# multiOsh2.net
KiCad netlist of a schematic drawn in EAGLE
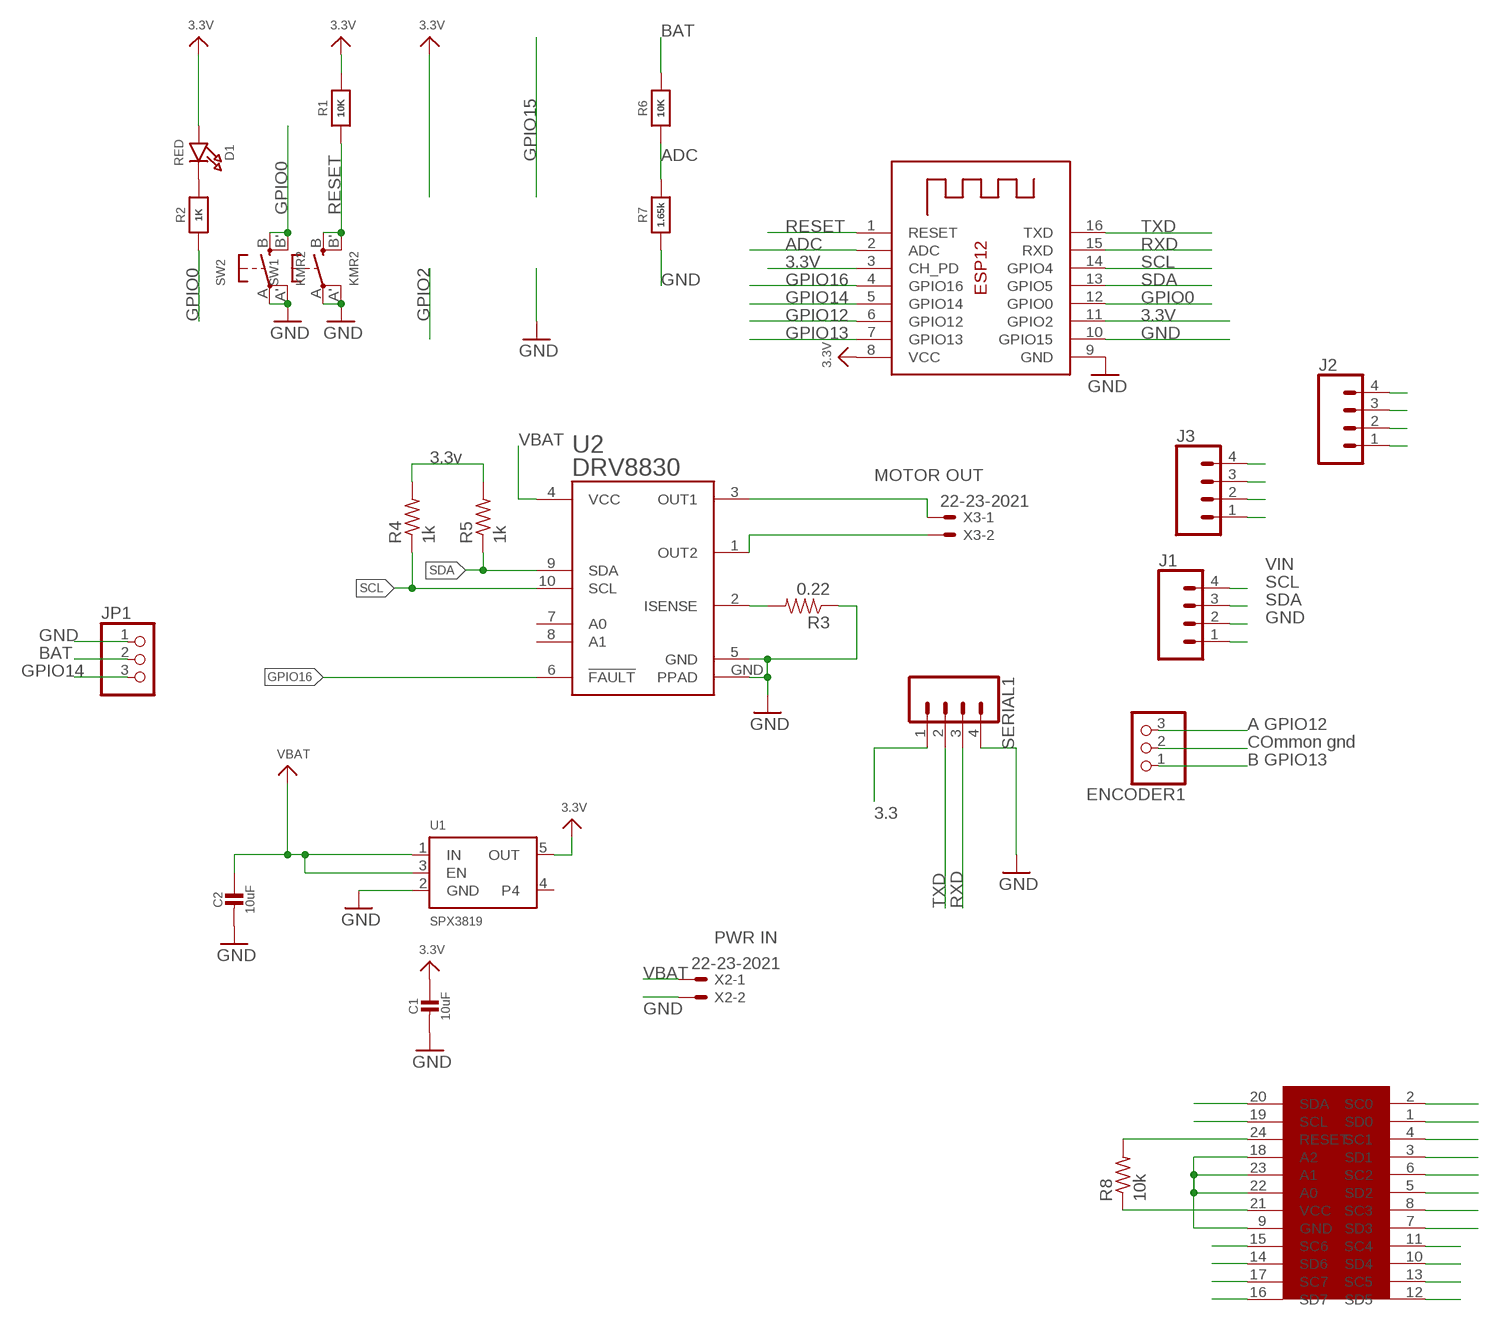
[diagram p0: schematic, sheet 1, part 1 of 3]
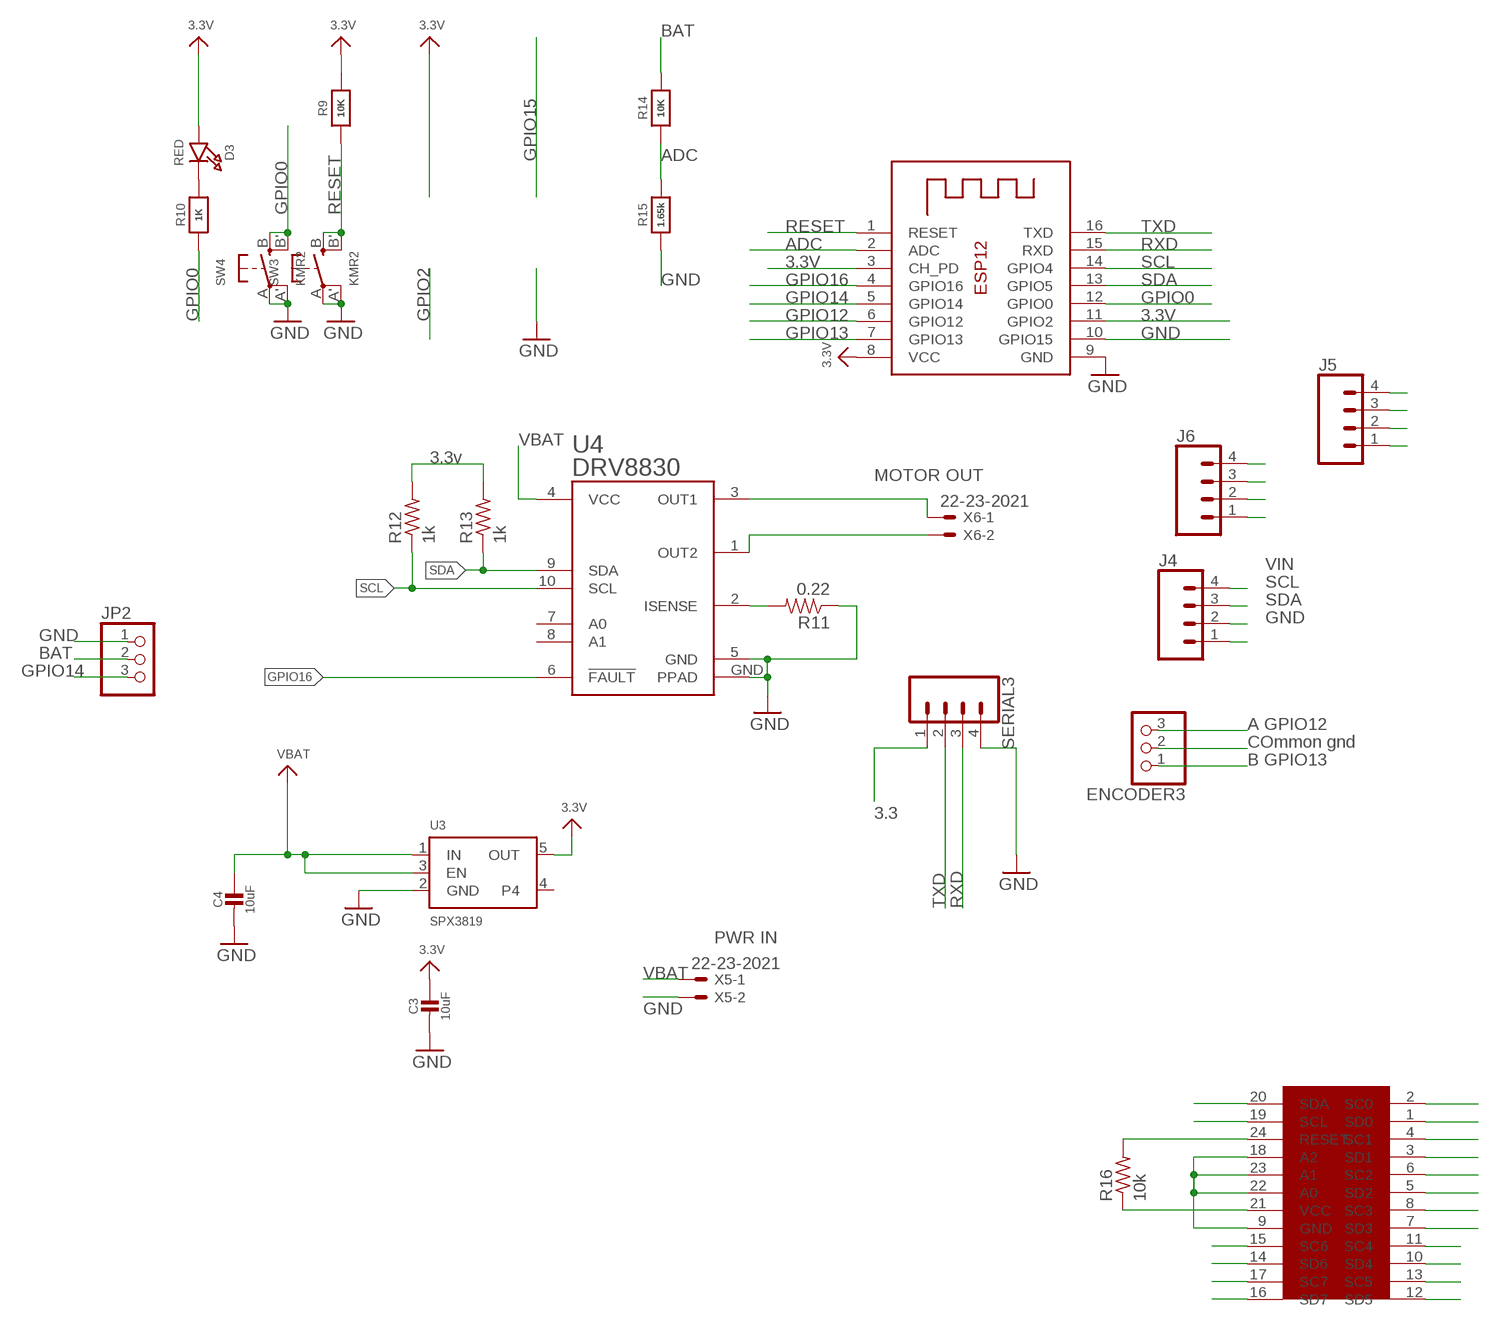
[diagram p1: schematic, sheet 1, part 2 of 3]
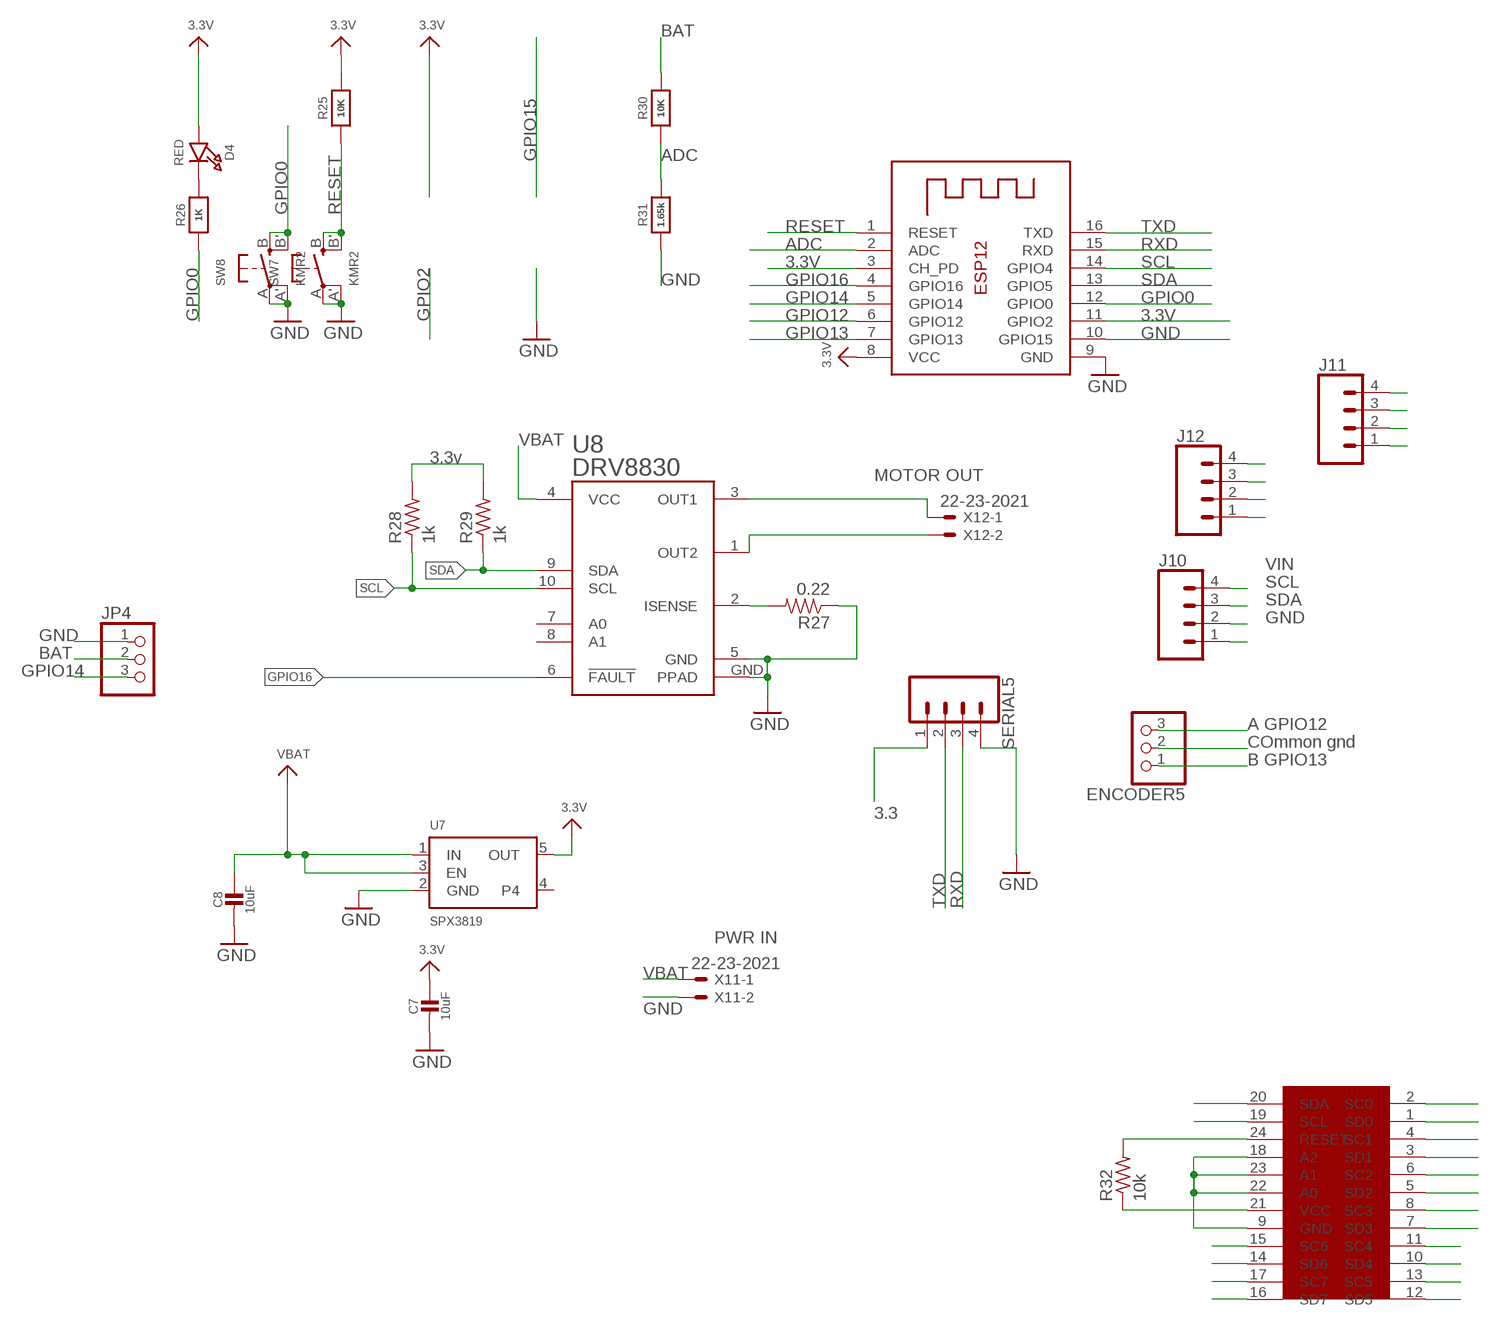
[diagram p2: schematic, sheet 1, part 3 of 3]

(export (version "E")
  (design (tool "Eeschema 10.0.6"))
  (components
    (comp (ref "C1")
      (value "10uF")
      (footprint "eagle-import:0805-NO")
      (libsource (lib "eagle-import") (part "CAP_CERAMIC0805-NOOUTLINE"))
    )
    (comp (ref "C2")
      (value "10uF")
      (footprint "eagle-import:0805-NO")
      (libsource (lib "eagle-import") (part "CAP_CERAMIC0805-NOOUTLINE"))
    )
    (comp (ref "C3")
      (value "10uF")
      (footprint "eagle-import:0805-NO")
      (libsource (lib "eagle-import") (part "CAP_CERAMIC0805-NOOUTLINE"))
    )
    (comp (ref "C4")
      (value "10uF")
      (footprint "eagle-import:0805-NO")
      (libsource (lib "eagle-import") (part "CAP_CERAMIC0805-NOOUTLINE"))
    )
    (comp (ref "C7")
      (value "10uF")
      (footprint "eagle-import:0805-NO")
      (libsource (lib "eagle-import") (part "CAP_CERAMIC0805-NOOUTLINE"))
    )
    (comp (ref "C8")
      (value "10uF")
      (footprint "eagle-import:0805-NO")
      (libsource (lib "eagle-import") (part "CAP_CERAMIC0805-NOOUTLINE"))
    )
    (comp (ref "D1")
      (value "RED")
      (footprint "eagle-import:CHIPLED_0805_NOOUTLINE")
      (libsource (lib "eagle-import") (part "LED0805_NOOUTLINE"))
    )
    (comp (ref "D3")
      (value "RED")
      (footprint "eagle-import:CHIPLED_0805_NOOUTLINE")
      (libsource (lib "eagle-import") (part "LED0805_NOOUTLINE"))
    )
    (comp (ref "D4")
      (value "RED")
      (footprint "eagle-import:CHIPLED_0805_NOOUTLINE")
      (libsource (lib "eagle-import") (part "LED0805_NOOUTLINE"))
    )
    (comp (ref "ENCODER1")
      (value "PINHD-1X3")
      (footprint "eagle-import:1X03")
      (libsource (lib "eagle-import") (part "PINHD-1X3"))
    )
    (comp (ref "ENCODER3")
      (value "PINHD-1X3")
      (footprint "eagle-import:1X03")
      (libsource (lib "eagle-import") (part "PINHD-1X3"))
    )
    (comp (ref "ENCODER5")
      (value "PINHD-1X3")
      (footprint "eagle-import:1X03")
      (libsource (lib "eagle-import") (part "PINHD-1X3"))
    )
    (comp (ref "J1")
      (value "CONN_04")
      (footprint "eagle-import:1X04")
      (libsource (lib "eagle-import") (part "CONN_04"))
    )
    (comp (ref "J2")
      (value "CONN_04")
      (footprint "eagle-import:1X04")
      (libsource (lib "eagle-import") (part "CONN_04"))
    )
    (comp (ref "J3")
      (value "CONN_04")
      (footprint "eagle-import:1X04")
      (libsource (lib "eagle-import") (part "CONN_04"))
    )
    (comp (ref "J4")
      (value "CONN_04")
      (footprint "eagle-import:1X04")
      (libsource (lib "eagle-import") (part "CONN_04"))
    )
    (comp (ref "J5")
      (value "CONN_04")
      (footprint "eagle-import:1X04")
      (libsource (lib "eagle-import") (part "CONN_04"))
    )
    (comp (ref "J6")
      (value "CONN_04")
      (footprint "eagle-import:1X04")
      (libsource (lib "eagle-import") (part "CONN_04"))
    )
    (comp (ref "J10")
      (value "CONN_04")
      (footprint "eagle-import:1X04")
      (libsource (lib "eagle-import") (part "CONN_04"))
    )
    (comp (ref "J11")
      (value "CONN_04")
      (footprint "eagle-import:1X04")
      (libsource (lib "eagle-import") (part "CONN_04"))
    )
    (comp (ref "J12")
      (value "CONN_04")
      (footprint "eagle-import:1X04")
      (libsource (lib "eagle-import") (part "CONN_04"))
    )
    (comp (ref "JP1")
      (value "PINHD-1X3")
      (footprint "eagle-import:1X03")
      (libsource (lib "eagle-import") (part "PINHD-1X3"))
    )
    (comp (ref "JP2")
      (value "PINHD-1X3")
      (footprint "eagle-import:1X03")
      (libsource (lib "eagle-import") (part "PINHD-1X3"))
    )
    (comp (ref "JP4")
      (value "PINHD-1X3")
      (footprint "eagle-import:1X03")
      (libsource (lib "eagle-import") (part "PINHD-1X3"))
    )
    (comp (ref "R1")
      (value "10K")
      (footprint "eagle-import:0805-NO")
      (libsource (lib "eagle-import") (part "RESISTOR0805_NOOUTLINE"))
    )
    (comp (ref "R2")
      (value "1K")
      (footprint "eagle-import:0805-NO")
      (libsource (lib "eagle-import") (part "RESISTOR0805_NOOUTLINE"))
    )
    (comp (ref "R3")
      (value "0.22")
      (footprint "eagle-import:0805")
      (libsource (lib "eagle-import") (part "0.22OHM1/4W1%(0805)"))
    )
    (comp (ref "R4")
      (value "1k")
      (footprint "eagle-import:R0805")
      (libsource (lib "eagle-import") (part "R-US_R0805"))
    )
    (comp (ref "R5")
      (value "1k")
      (footprint "eagle-import:R0805")
      (libsource (lib "eagle-import") (part "R-US_R0805"))
    )
    (comp (ref "R6")
      (value "10K")
      (footprint "eagle-import:0805-NO")
      (libsource (lib "eagle-import") (part "RESISTOR0805_NOOUTLINE"))
    )
    (comp (ref "R7")
      (value "1.65k")
      (footprint "eagle-import:0805-NO")
      (libsource (lib "eagle-import") (part "RESISTOR0805_NOOUTLINE"))
    )
    (comp (ref "R8")
      (value "10k")
      (footprint "eagle-import:M0805")
      (libsource (lib "eagle-import") (part "R-US_M0805"))
    )
    (comp (ref "R9")
      (value "10K")
      (footprint "eagle-import:0805-NO")
      (libsource (lib "eagle-import") (part "RESISTOR0805_NOOUTLINE"))
    )
    (comp (ref "R10")
      (value "1K")
      (footprint "eagle-import:0805-NO")
      (libsource (lib "eagle-import") (part "RESISTOR0805_NOOUTLINE"))
    )
    (comp (ref "R11")
      (value "0.22")
      (footprint "eagle-import:0805")
      (libsource (lib "eagle-import") (part "0.22OHM1/4W1%(0805)"))
    )
    (comp (ref "R12")
      (value "1k")
      (footprint "eagle-import:R0805")
      (libsource (lib "eagle-import") (part "R-US_R0805"))
    )
    (comp (ref "R13")
      (value "1k")
      (footprint "eagle-import:R0805")
      (libsource (lib "eagle-import") (part "R-US_R0805"))
    )
    (comp (ref "R14")
      (value "10K")
      (footprint "eagle-import:0805-NO")
      (libsource (lib "eagle-import") (part "RESISTOR0805_NOOUTLINE"))
    )
    (comp (ref "R15")
      (value "1.65k")
      (footprint "eagle-import:0805-NO")
      (libsource (lib "eagle-import") (part "RESISTOR0805_NOOUTLINE"))
    )
    (comp (ref "R16")
      (value "10k")
      (footprint "eagle-import:M0805")
      (libsource (lib "eagle-import") (part "R-US_M0805"))
    )
    (comp (ref "R25")
      (value "10K")
      (footprint "eagle-import:0805-NO")
      (libsource (lib "eagle-import") (part "RESISTOR0805_NOOUTLINE"))
    )
    (comp (ref "R26")
      (value "1K")
      (footprint "eagle-import:0805-NO")
      (libsource (lib "eagle-import") (part "RESISTOR0805_NOOUTLINE"))
    )
    (comp (ref "R27")
      (value "0.22")
      (footprint "eagle-import:0805")
      (libsource (lib "eagle-import") (part "0.22OHM1/4W1%(0805)"))
    )
    (comp (ref "R28")
      (value "1k")
      (footprint "eagle-import:R0805")
      (libsource (lib "eagle-import") (part "R-US_R0805"))
    )
    (comp (ref "R29")
      (value "1k")
      (footprint "eagle-import:R0805")
      (libsource (lib "eagle-import") (part "R-US_R0805"))
    )
    (comp (ref "R30")
      (value "10K")
      (footprint "eagle-import:0805-NO")
      (libsource (lib "eagle-import") (part "RESISTOR0805_NOOUTLINE"))
    )
    (comp (ref "R31")
      (value "1.65k")
      (footprint "eagle-import:0805-NO")
      (libsource (lib "eagle-import") (part "RESISTOR0805_NOOUTLINE"))
    )
    (comp (ref "R32")
      (value "10k")
      (footprint "eagle-import:M0805")
      (libsource (lib "eagle-import") (part "R-US_M0805"))
    )
    (comp (ref "SERIAL1")
      (value "CONN_04")
      (footprint "eagle-import:1X04")
      (libsource (lib "eagle-import") (part "CONN_04"))
    )
    (comp (ref "SERIAL3")
      (value "CONN_04")
      (footprint "eagle-import:1X04")
      (libsource (lib "eagle-import") (part "CONN_04"))
    )
    (comp (ref "SERIAL5")
      (value "CONN_04")
      (footprint "eagle-import:1X04")
      (libsource (lib "eagle-import") (part "CONN_04"))
    )
    (comp (ref "SW1")
      (value "KMR2")
      (footprint "eagle-import:BTN_KMR2_4.6X2.8")
      (libsource (lib "eagle-import") (part "SWITCH_TACT_SMT4.6X2.8"))
    )
    (comp (ref "SW2")
      (value "KMR2")
      (footprint "eagle-import:BTN_KMR2_4.6X2.8")
      (libsource (lib "eagle-import") (part "SWITCH_TACT_SMT4.6X2.8"))
    )
    (comp (ref "SW3")
      (value "KMR2")
      (footprint "eagle-import:BTN_KMR2_4.6X2.8")
      (libsource (lib "eagle-import") (part "SWITCH_TACT_SMT4.6X2.8"))
    )
    (comp (ref "SW4")
      (value "KMR2")
      (footprint "eagle-import:BTN_KMR2_4.6X2.8")
      (libsource (lib "eagle-import") (part "SWITCH_TACT_SMT4.6X2.8"))
    )
    (comp (ref "SW7")
      (value "KMR2")
      (footprint "eagle-import:BTN_KMR2_4.6X2.8")
      (libsource (lib "eagle-import") (part "SWITCH_TACT_SMT4.6X2.8"))
    )
    (comp (ref "SW8")
      (value "KMR2")
      (footprint "eagle-import:BTN_KMR2_4.6X2.8")
      (libsource (lib "eagle-import") (part "SWITCH_TACT_SMT4.6X2.8"))
    )
    (comp (ref "U$8")
      (value "TCA9548A")
      (footprint "eagle-import:QFN24-4X4")
      (libsource (lib "eagle-import") (part "TCA9548A"))
    )
    (comp (ref "U$16")
      (value "TCA9548A")
      (footprint "eagle-import:QFN24-4X4")
      (libsource (lib "eagle-import") (part "TCA9548A"))
    )
    (comp (ref "U$35")
      (value "TCA9548A")
      (footprint "eagle-import:QFN24-4X4")
      (libsource (lib "eagle-import") (part "TCA9548A"))
    )
    (comp (ref "U1")
      (value "SPX3819")
      (footprint "eagle-import:SOT23-5")
      (libsource (lib "eagle-import") (part "VREG_SOT23-5"))
    )
    (comp (ref "U2")
      (value "DRV8830")
      (footprint "eagle-import:MSOP-10-GNDPAD")
      (libsource (lib "eagle-import") (part "DRV8830"))
    )
    (comp (ref "U3")
      (value "SPX3819")
      (footprint "eagle-import:SOT23-5")
      (libsource (lib "eagle-import") (part "VREG_SOT23-5"))
    )
    (comp (ref "U4")
      (value "DRV8830")
      (footprint "eagle-import:MSOP-10-GNDPAD")
      (libsource (lib "eagle-import") (part "DRV8830"))
    )
    (comp (ref "U7")
      (value "SPX3819")
      (footprint "eagle-import:SOT23-5")
      (libsource (lib "eagle-import") (part "VREG_SOT23-5"))
    )
    (comp (ref "U8")
      (value "DRV8830")
      (footprint "eagle-import:MSOP-10-GNDPAD")
      (libsource (lib "eagle-import") (part "DRV8830"))
    )
    (comp (ref "X1")
      (value "ESP-12")
      (footprint "eagle-import:ESP-12")
      (libsource (lib "eagle-import") (part "ESP-12"))
    )
    (comp (ref "X2")
      (value "22-23-2021")
      (footprint "eagle-import:22-23-2021")
      (fields (field (name "MF") "MOLEX"))
      (libsource (lib "eagle-import") (part "22-23-2021"))
    )
    (comp (ref "X3")
      (value "22-23-2021")
      (footprint "eagle-import:22-23-2021")
      (fields (field (name "MF") "MOLEX"))
      (libsource (lib "eagle-import") (part "22-23-2021"))
    )
    (comp (ref "X4")
      (value "ESP-12")
      (footprint "eagle-import:ESP-12")
      (libsource (lib "eagle-import") (part "ESP-12"))
    )
    (comp (ref "X5")
      (value "22-23-2021")
      (footprint "eagle-import:22-23-2021")
      (fields (field (name "MF") "MOLEX"))
      (libsource (lib "eagle-import") (part "22-23-2021"))
    )
    (comp (ref "X6")
      (value "22-23-2021")
      (footprint "eagle-import:22-23-2021")
      (fields (field (name "MF") "MOLEX"))
      (libsource (lib "eagle-import") (part "22-23-2021"))
    )
    (comp (ref "X10")
      (value "ESP-12")
      (footprint "eagle-import:ESP-12")
      (libsource (lib "eagle-import") (part "ESP-12"))
    )
    (comp (ref "X11")
      (value "22-23-2021")
      (footprint "eagle-import:22-23-2021")
      (fields (field (name "MF") "MOLEX"))
      (libsource (lib "eagle-import") (part "22-23-2021"))
    )
    (comp (ref "X12")
      (value "22-23-2021")
      (footprint "eagle-import:22-23-2021")
      (fields (field (name "MF") "MOLEX"))
      (libsource (lib "eagle-import") (part "22-23-2021"))
    )
  )
  (nets
    (net (code "1") (name "/ADC") (class "Default")
      (node (ref "R14") (pin "1") (pinfunction "1_1") (pintype "passive"))
      (node (ref "R15") (pin "2") (pinfunction "2_2") (pintype "passive"))
      (node (ref "R30") (pin "1") (pinfunction "1_1") (pintype "passive"))
      (node (ref "R31") (pin "2") (pinfunction "2_2") (pintype "passive"))
      (node (ref "R6") (pin "1") (pinfunction "1_1") (pintype "passive"))
      (node (ref "R7") (pin "2") (pinfunction "2_2") (pintype "passive"))
      (node (ref "X1") (pin "2") (pinfunction "ADC_2") (pintype "passive"))
      (node (ref "X10") (pin "2") (pinfunction "ADC_2") (pintype "passive"))
      (node (ref "X4") (pin "2") (pinfunction "ADC_2") (pintype "passive"))
    )
    (net (code "2") (name "/GPIO0") (class "Default")
      (node (ref "R10") (pin "1") (pinfunction "1_1") (pintype "passive"))
      (node (ref "R2") (pin "1") (pinfunction "1_1") (pintype "passive"))
      (node (ref "R26") (pin "1") (pinfunction "1_1") (pintype "passive"))
      (node (ref "SW2") (pin "B") (pinfunction "S_B") (pintype "passive"))
      (node (ref "SW2") (pin "B'") (pinfunction "S1_B'") (pintype "passive"))
      (node (ref "SW4") (pin "B") (pinfunction "S_B") (pintype "passive"))
      (node (ref "SW4") (pin "B'") (pinfunction "S1_B'") (pintype "passive"))
      (node (ref "SW8") (pin "B") (pinfunction "S_B") (pintype "passive"))
      (node (ref "SW8") (pin "B'") (pinfunction "S1_B'") (pintype "passive"))
      (node (ref "X1") (pin "12") (pinfunction "GPIO0_12") (pintype "bidirectional"))
      (node (ref "X10") (pin "12") (pinfunction "GPIO0_12") (pintype "bidirectional"))
      (node (ref "X4") (pin "12") (pinfunction "GPIO0_12") (pintype "bidirectional"))
    )
    (net (code "4") (name "/GPIO12") (class "Default")
      (node (ref "ENCODER1") (pin "3") (pinfunction "3_3") (pintype "passive"))
      (node (ref "ENCODER3") (pin "3") (pinfunction "3_3") (pintype "passive"))
      (node (ref "ENCODER5") (pin "3") (pinfunction "3_3") (pintype "passive"))
      (node (ref "X1") (pin "6") (pinfunction "GPIO12_6") (pintype "bidirectional"))
      (node (ref "X10") (pin "6") (pinfunction "GPIO12_6") (pintype "bidirectional"))
      (node (ref "X4") (pin "6") (pinfunction "GPIO12_6") (pintype "bidirectional"))
    )
    (net (code "5") (name "/GPIO13") (class "Default")
      (node (ref "ENCODER1") (pin "1") (pinfunction "1_1") (pintype "passive"))
      (node (ref "ENCODER3") (pin "1") (pinfunction "1_1") (pintype "passive"))
      (node (ref "ENCODER5") (pin "1") (pinfunction "1_1") (pintype "passive"))
      (node (ref "X1") (pin "7") (pinfunction "GPIO13_7") (pintype "bidirectional"))
      (node (ref "X10") (pin "7") (pinfunction "GPIO13_7") (pintype "bidirectional"))
      (node (ref "X4") (pin "7") (pinfunction "GPIO13_7") (pintype "bidirectional"))
    )
    (net (code "6") (name "/GPIO14") (class "Default")
      (node (ref "JP1") (pin "3") (pinfunction "3_3") (pintype "passive"))
      (node (ref "JP2") (pin "3") (pinfunction "3_3") (pintype "passive"))
      (node (ref "JP4") (pin "3") (pinfunction "3_3") (pintype "passive"))
      (node (ref "X1") (pin "5") (pinfunction "GPIO14_5") (pintype "bidirectional"))
      (node (ref "X10") (pin "5") (pinfunction "GPIO14_5") (pintype "bidirectional"))
      (node (ref "X4") (pin "5") (pinfunction "GPIO14_5") (pintype "bidirectional"))
    )
    (net (code "8") (name "/RESET") (class "Default")
      (node (ref "R1") (pin "1") (pinfunction "1_1") (pintype "passive"))
      (node (ref "R25") (pin "1") (pinfunction "1_1") (pintype "passive"))
      (node (ref "R9") (pin "1") (pinfunction "1_1") (pintype "passive"))
      (node (ref "SW1") (pin "B") (pinfunction "S_B") (pintype "passive"))
      (node (ref "SW1") (pin "B'") (pinfunction "S1_B'") (pintype "passive"))
      (node (ref "SW3") (pin "B") (pinfunction "S_B") (pintype "passive"))
      (node (ref "SW3") (pin "B'") (pinfunction "S1_B'") (pintype "passive"))
      (node (ref "SW7") (pin "B") (pinfunction "S_B") (pintype "passive"))
      (node (ref "SW7") (pin "B'") (pinfunction "S1_B'") (pintype "passive"))
      (node (ref "X1") (pin "1") (pinfunction "RESET_1") (pintype "input"))
      (node (ref "X10") (pin "1") (pinfunction "RESET_1") (pintype "input"))
      (node (ref "X4") (pin "1") (pinfunction "RESET_1") (pintype "input"))
    )
    (net (code "9") (name "/RXD") (class "Default")
      (node (ref "SERIAL1") (pin "3") (pinfunction "3_3") (pintype "passive"))
      (node (ref "SERIAL3") (pin "3") (pinfunction "3_3") (pintype "passive"))
      (node (ref "SERIAL5") (pin "3") (pinfunction "3_3") (pintype "passive"))
      (node (ref "X1") (pin "15") (pinfunction "RXD_15") (pintype "input"))
      (node (ref "X10") (pin "15") (pinfunction "RXD_15") (pintype "input"))
      (node (ref "X4") (pin "15") (pinfunction "RXD_15") (pintype "input"))
    )
    (net (code "10") (name "/SC4") (class "Default")
      (node (ref "J3") (pin "2") (pinfunction "2_2") (pintype "passive"))
      (node (ref "U$8") (pin "8") (pinfunction "SC3_8") (pintype "bidirectional"))
    )
    (net (code "11") (name "/SC5") (class "Default")
      (node (ref "J1") (pin "2") (pinfunction "2_2") (pintype "passive"))
      (node (ref "U$8") (pin "15") (pinfunction "SC6_15") (pintype "bidirectional"))
    )
    (net (code "12") (name "/SC8") (class "Default")
      (node (ref "J2") (pin "2") (pinfunction "2_2") (pintype "passive"))
      (node (ref "U$8") (pin "13") (pinfunction "SC5_13") (pintype "bidirectional"))
    )
    (net (code "13") (name "/SC12") (class "Default")
      (node (ref "J6") (pin "2") (pinfunction "2_2") (pintype "passive"))
      (node (ref "U$16") (pin "8") (pinfunction "SC3_8") (pintype "bidirectional"))
    )
    (net (code "14") (name "/SC13") (class "Default")
      (node (ref "J4") (pin "2") (pinfunction "2_2") (pintype "passive"))
      (node (ref "U$16") (pin "15") (pinfunction "SC6_15") (pintype "bidirectional"))
    )
    (net (code "15") (name "/SC24") (class "Default")
      (node (ref "J5") (pin "2") (pinfunction "2_2") (pintype "passive"))
      (node (ref "U$16") (pin "13") (pinfunction "SC5_13") (pintype "bidirectional"))
    )
    (net (code "16") (name "/SC28") (class "Default")
      (node (ref "J12") (pin "2") (pinfunction "2_2") (pintype "passive"))
      (node (ref "U$35") (pin "8") (pinfunction "SC3_8") (pintype "bidirectional"))
    )
    (net (code "17") (name "/SC29") (class "Default")
      (node (ref "J10") (pin "2") (pinfunction "2_2") (pintype "passive"))
      (node (ref "U$35") (pin "15") (pinfunction "SC6_15") (pintype "bidirectional"))
    )
    (net (code "18") (name "/SC40") (class "Default")
      (node (ref "J11") (pin "2") (pinfunction "2_2") (pintype "passive"))
      (node (ref "U$35") (pin "13") (pinfunction "SC5_13") (pintype "bidirectional"))
    )
    (net (code "19") (name "/SD4") (class "Default")
      (node (ref "J3") (pin "3") (pinfunction "3_3") (pintype "passive"))
      (node (ref "U$8") (pin "7") (pinfunction "SD3_7") (pintype "bidirectional"))
    )
    (net (code "20") (name "/SD5") (class "Default")
      (node (ref "J1") (pin "3") (pinfunction "3_3") (pintype "passive"))
      (node (ref "U$8") (pin "14") (pinfunction "SD6_14") (pintype "bidirectional"))
    )
    (net (code "21") (name "/SD8") (class "Default")
      (node (ref "J2") (pin "3") (pinfunction "3_3") (pintype "passive"))
      (node (ref "U$8") (pin "12") (pinfunction "SD5_12") (pintype "bidirectional"))
    )
    (net (code "22") (name "/SD12") (class "Default")
      (node (ref "J6") (pin "3") (pinfunction "3_3") (pintype "passive"))
      (node (ref "U$16") (pin "7") (pinfunction "SD3_7") (pintype "bidirectional"))
    )
    (net (code "23") (name "/SD13") (class "Default")
      (node (ref "J4") (pin "3") (pinfunction "3_3") (pintype "passive"))
      (node (ref "U$16") (pin "14") (pinfunction "SD6_14") (pintype "bidirectional"))
    )
    (net (code "24") (name "/SD24") (class "Default")
      (node (ref "J5") (pin "3") (pinfunction "3_3") (pintype "passive"))
      (node (ref "U$16") (pin "12") (pinfunction "SD5_12") (pintype "bidirectional"))
    )
    (net (code "25") (name "/SD28") (class "Default")
      (node (ref "J12") (pin "3") (pinfunction "3_3") (pintype "passive"))
      (node (ref "U$35") (pin "7") (pinfunction "SD3_7") (pintype "bidirectional"))
    )
    (net (code "26") (name "/SD29") (class "Default")
      (node (ref "J10") (pin "3") (pinfunction "3_3") (pintype "passive"))
      (node (ref "U$35") (pin "14") (pinfunction "SD6_14") (pintype "bidirectional"))
    )
    (net (code "27") (name "/SD40") (class "Default")
      (node (ref "J11") (pin "3") (pinfunction "3_3") (pintype "passive"))
      (node (ref "U$35") (pin "12") (pinfunction "SD5_12") (pintype "bidirectional"))
    )
    (net (code "28") (name "/TXD") (class "Default")
      (node (ref "SERIAL1") (pin "2") (pinfunction "2_2") (pintype "passive"))
      (node (ref "SERIAL3") (pin "2") (pinfunction "2_2") (pintype "passive"))
      (node (ref "SERIAL5") (pin "2") (pinfunction "2_2") (pintype "passive"))
      (node (ref "X1") (pin "16") (pinfunction "TXD_16") (pintype "output"))
      (node (ref "X10") (pin "16") (pinfunction "TXD_16") (pintype "output"))
      (node (ref "X4") (pin "16") (pinfunction "TXD_16") (pintype "output"))
    )
    (net (code "29") (name "3.3V") (class "Default")
      (node (ref "C1") (pin "1") (pinfunction "1_1") (pintype "passive"))
      (node (ref "C3") (pin "1") (pinfunction "1_1") (pintype "passive"))
      (node (ref "C7") (pin "1") (pinfunction "1_1") (pintype "passive"))
      (node (ref "D1") (pin "A") (pinfunction "A_A") (pintype "passive"))
      (node (ref "D3") (pin "A") (pinfunction "A_A") (pintype "passive"))
      (node (ref "D4") (pin "A") (pinfunction "A_A") (pintype "passive"))
      (node (ref "J1") (pin "4") (pinfunction "4_4") (pintype "passive"))
      (node (ref "J10") (pin "4") (pinfunction "4_4") (pintype "passive"))
      (node (ref "J11") (pin "4") (pinfunction "4_4") (pintype "passive"))
      (node (ref "J12") (pin "4") (pinfunction "4_4") (pintype "passive"))
      (node (ref "J2") (pin "4") (pinfunction "4_4") (pintype "passive"))
      (node (ref "J3") (pin "4") (pinfunction "4_4") (pintype "passive"))
      (node (ref "J4") (pin "4") (pinfunction "4_4") (pintype "passive"))
      (node (ref "J5") (pin "4") (pinfunction "4_4") (pintype "passive"))
      (node (ref "J6") (pin "4") (pinfunction "4_4") (pintype "passive"))
      (node (ref "R1") (pin "2") (pinfunction "2_2") (pintype "passive"))
      (node (ref "R12") (pin "2") (pinfunction "2_2") (pintype "passive"))
      (node (ref "R13") (pin "2") (pinfunction "2_2") (pintype "passive"))
      (node (ref "R16") (pin "1") (pinfunction "1_1") (pintype "passive"))
      (node (ref "R25") (pin "2") (pinfunction "2_2") (pintype "passive"))
      (node (ref "R28") (pin "2") (pinfunction "2_2") (pintype "passive"))
      (node (ref "R29") (pin "2") (pinfunction "2_2") (pintype "passive"))
      (node (ref "R32") (pin "1") (pinfunction "1_1") (pintype "passive"))
      (node (ref "R4") (pin "2") (pinfunction "2_2") (pintype "passive"))
      (node (ref "R5") (pin "2") (pinfunction "2_2") (pintype "passive"))
      (node (ref "R8") (pin "1") (pinfunction "1_1") (pintype "passive"))
      (node (ref "R9") (pin "2") (pinfunction "2_2") (pintype "passive"))
      (node (ref "SERIAL1") (pin "1") (pinfunction "1_1") (pintype "passive"))
      (node (ref "SERIAL3") (pin "1") (pinfunction "1_1") (pintype "passive"))
      (node (ref "SERIAL5") (pin "1") (pinfunction "1_1") (pintype "passive"))
      (node (ref "U$16") (pin "21") (pinfunction "VCC_21") (pintype "bidirectional"))
      (node (ref "U$35") (pin "21") (pinfunction "VCC_21") (pintype "bidirectional"))
      (node (ref "U$8") (pin "21") (pinfunction "VCC_21") (pintype "bidirectional"))
      (node (ref "U1") (pin "5") (pinfunction "OUT_5") (pintype "power_in"))
      (node (ref "U3") (pin "5") (pinfunction "OUT_5") (pintype "power_in"))
      (node (ref "U7") (pin "5") (pinfunction "OUT_5") (pintype "power_in"))
      (node (ref "X1") (pin "11") (pinfunction "GPIO2_11") (pintype "bidirectional"))
      (node (ref "X1") (pin "3") (pinfunction "CH_PD_3") (pintype "input"))
      (node (ref "X1") (pin "8") (pinfunction "VCC_8") (pintype "power_in"))
      (node (ref "X10") (pin "11") (pinfunction "GPIO2_11") (pintype "bidirectional"))
      (node (ref "X10") (pin "3") (pinfunction "CH_PD_3") (pintype "input"))
      (node (ref "X10") (pin "8") (pinfunction "VCC_8") (pintype "power_in"))
      (node (ref "X4") (pin "11") (pinfunction "GPIO2_11") (pintype "bidirectional"))
      (node (ref "X4") (pin "3") (pinfunction "CH_PD_3") (pintype "input"))
      (node (ref "X4") (pin "8") (pinfunction "VCC_8") (pintype "power_in"))
    )
    (net (code "30") (name "GND") (class "Default")
      (node (ref "C1") (pin "2") (pinfunction "2_2") (pintype "passive"))
      (node (ref "C2") (pin "2") (pinfunction "2_2") (pintype "passive"))
      (node (ref "C3") (pin "2") (pinfunction "2_2") (pintype "passive"))
      (node (ref "C4") (pin "2") (pinfunction "2_2") (pintype "passive"))
      (node (ref "C7") (pin "2") (pinfunction "2_2") (pintype "passive"))
      (node (ref "C8") (pin "2") (pinfunction "2_2") (pintype "passive"))
      (node (ref "ENCODER1") (pin "2") (pinfunction "2_2") (pintype "passive"))
      (node (ref "ENCODER3") (pin "2") (pinfunction "2_2") (pintype "passive"))
      (node (ref "ENCODER5") (pin "2") (pinfunction "2_2") (pintype "passive"))
      (node (ref "J1") (pin "1") (pinfunction "1_1") (pintype "passive"))
      (node (ref "J10") (pin "1") (pinfunction "1_1") (pintype "passive"))
      (node (ref "J11") (pin "1") (pinfunction "1_1") (pintype "passive"))
      (node (ref "J12") (pin "1") (pinfunction "1_1") (pintype "passive"))
      (node (ref "J2") (pin "1") (pinfunction "1_1") (pintype "passive"))
      (node (ref "J3") (pin "1") (pinfunction "1_1") (pintype "passive"))
      (node (ref "J4") (pin "1") (pinfunction "1_1") (pintype "passive"))
      (node (ref "J5") (pin "1") (pinfunction "1_1") (pintype "passive"))
      (node (ref "J6") (pin "1") (pinfunction "1_1") (pintype "passive"))
      (node (ref "JP1") (pin "1") (pinfunction "1_1") (pintype "passive"))
      (node (ref "JP2") (pin "1") (pinfunction "1_1") (pintype "passive"))
      (node (ref "JP4") (pin "1") (pinfunction "1_1") (pintype "passive"))
      (node (ref "R11") (pin "1") (pinfunction "1_1") (pintype "passive"))
      (node (ref "R15") (pin "1") (pinfunction "1_1") (pintype "passive"))
      (node (ref "R27") (pin "1") (pinfunction "1_1") (pintype "passive"))
      (node (ref "R3") (pin "1") (pinfunction "1_1") (pintype "passive"))
      (node (ref "R31") (pin "1") (pinfunction "1_1") (pintype "passive"))
      (node (ref "R7") (pin "1") (pinfunction "1_1") (pintype "passive"))
      (node (ref "SERIAL1") (pin "4") (pinfunction "4_4") (pintype "passive"))
      (node (ref "SERIAL3") (pin "4") (pinfunction "4_4") (pintype "passive"))
      (node (ref "SERIAL5") (pin "4") (pinfunction "4_4") (pintype "passive"))
      (node (ref "SW1") (pin "A") (pinfunction "P_A") (pintype "passive"))
      (node (ref "SW1") (pin "A'") (pinfunction "P1_A'") (pintype "passive"))
      (node (ref "SW2") (pin "A") (pinfunction "P_A") (pintype "passive"))
      (node (ref "SW2") (pin "A'") (pinfunction "P1_A'") (pintype "passive"))
      (node (ref "SW3") (pin "A") (pinfunction "P_A") (pintype "passive"))
      (node (ref "SW3") (pin "A'") (pinfunction "P1_A'") (pintype "passive"))
      (node (ref "SW4") (pin "A") (pinfunction "P_A") (pintype "passive"))
      (node (ref "SW4") (pin "A'") (pinfunction "P1_A'") (pintype "passive"))
      (node (ref "SW7") (pin "A") (pinfunction "P_A") (pintype "passive"))
      (node (ref "SW7") (pin "A'") (pinfunction "P1_A'") (pintype "passive"))
      (node (ref "SW8") (pin "A") (pinfunction "P_A") (pintype "passive"))
      (node (ref "SW8") (pin "A'") (pinfunction "P1_A'") (pintype "passive"))
      (node (ref "U$16") (pin "18") (pinfunction "A2_18") (pintype "bidirectional"))
      (node (ref "U$16") (pin "22") (pinfunction "A0_22") (pintype "bidirectional"))
      (node (ref "U$16") (pin "23") (pinfunction "A1_23") (pintype "bidirectional"))
      (node (ref "U$16") (pin "9") (pinfunction "GND_9") (pintype "bidirectional"))
      (node (ref "U$35") (pin "18") (pinfunction "A2_18") (pintype "bidirectional"))
      (node (ref "U$35") (pin "22") (pinfunction "A0_22") (pintype "bidirectional"))
      (node (ref "U$35") (pin "23") (pinfunction "A1_23") (pintype "bidirectional"))
      (node (ref "U$35") (pin "9") (pinfunction "GND_9") (pintype "bidirectional"))
      (node (ref "U$8") (pin "18") (pinfunction "A2_18") (pintype "bidirectional"))
      (node (ref "U$8") (pin "22") (pinfunction "A0_22") (pintype "bidirectional"))
      (node (ref "U$8") (pin "23") (pinfunction "A1_23") (pintype "bidirectional"))
      (node (ref "U$8") (pin "9") (pinfunction "GND_9") (pintype "bidirectional"))
      (node (ref "U1") (pin "2") (pinfunction "GND_2") (pintype "power_in"))
      (node (ref "U2") (pin "5") (pinfunction "GND_5") (pintype "bidirectional"))
      (node (ref "U2") (pin "GND") (pinfunction "PPAD_GND") (pintype "bidirectional"))
      (node (ref "U3") (pin "2") (pinfunction "GND_2") (pintype "power_in"))
      (node (ref "U4") (pin "5") (pinfunction "GND_5") (pintype "bidirectional"))
      (node (ref "U4") (pin "GND") (pinfunction "PPAD_GND") (pintype "bidirectional"))
      (node (ref "U7") (pin "2") (pinfunction "GND_2") (pintype "power_in"))
      (node (ref "U8") (pin "5") (pinfunction "GND_5") (pintype "bidirectional"))
      (node (ref "U8") (pin "GND") (pinfunction "PPAD_GND") (pintype "bidirectional"))
      (node (ref "X1") (pin "10") (pinfunction "GPIO15_10") (pintype "bidirectional"))
      (node (ref "X1") (pin "9") (pinfunction "GND_9") (pintype "power_in"))
      (node (ref "X10") (pin "10") (pinfunction "GPIO15_10") (pintype "bidirectional"))
      (node (ref "X10") (pin "9") (pinfunction "GND_9") (pintype "power_in"))
      (node (ref "X11") (pin "2") (pinfunction "S_2") (pintype "passive"))
      (node (ref "X2") (pin "2") (pinfunction "S_2") (pintype "passive"))
      (node (ref "X4") (pin "10") (pinfunction "GPIO15_10") (pintype "bidirectional"))
      (node (ref "X4") (pin "9") (pinfunction "GND_9") (pintype "power_in"))
      (node (ref "X5") (pin "2") (pinfunction "S_2") (pintype "passive"))
    )
    (net (code "31") (name "GPIO16") (class "Default")
      (node (ref "U2") (pin "6") (pinfunction "~{FAULT}_6") (pintype "bidirectional"))
      (node (ref "U4") (pin "6") (pinfunction "~{FAULT}_6") (pintype "bidirectional"))
      (node (ref "U8") (pin "6") (pinfunction "~{FAULT}_6") (pintype "bidirectional"))
      (node (ref "X1") (pin "4") (pinfunction "GPIO16_4") (pintype "bidirectional"))
      (node (ref "X10") (pin "4") (pinfunction "GPIO16_4") (pintype "bidirectional"))
      (node (ref "X4") (pin "4") (pinfunction "GPIO16_4") (pintype "bidirectional"))
    )
    (net (code "32") (name "Net-(D1-PadC)") (class "Default")
      (node (ref "D1") (pin "C") (pinfunction "C_C") (pintype "passive"))
      (node (ref "R2") (pin "2") (pinfunction "2_2") (pintype "passive"))
    )
    (net (code "33") (name "Net-(D3-PadC)") (class "Default")
      (node (ref "D3") (pin "C") (pinfunction "C_C") (pintype "passive"))
      (node (ref "R10") (pin "2") (pinfunction "2_2") (pintype "passive"))
    )
    (net (code "34") (name "Net-(D4-PadC)") (class "Default")
      (node (ref "D4") (pin "C") (pinfunction "C_C") (pintype "passive"))
      (node (ref "R26") (pin "2") (pinfunction "2_2") (pintype "passive"))
    )
    (net (code "35") (name "Net-(U$8-RESET)") (class "Default")
      (node (ref "R8") (pin "2") (pinfunction "2_2") (pintype "passive"))
      (node (ref "U$8") (pin "24") (pinfunction "RESET_24") (pintype "bidirectional"))
    )
    (net (code "36") (name "Net-(U$16-RESET)") (class "Default")
      (node (ref "R16") (pin "2") (pinfunction "2_2") (pintype "passive"))
      (node (ref "U$16") (pin "24") (pinfunction "RESET_24") (pintype "bidirectional"))
    )
    (net (code "37") (name "Net-(U$35-RESET)") (class "Default")
      (node (ref "R32") (pin "2") (pinfunction "2_2") (pintype "passive"))
      (node (ref "U$35") (pin "24") (pinfunction "RESET_24") (pintype "bidirectional"))
    )
    (net (code "38") (name "Net-(U2-ISENSE)") (class "Default")
      (node (ref "R3") (pin "2") (pinfunction "2_2") (pintype "passive"))
      (node (ref "U2") (pin "2") (pinfunction "ISENSE_2") (pintype "bidirectional"))
    )
    (net (code "39") (name "Net-(U2-OUT1)") (class "Default")
      (node (ref "U2") (pin "3") (pinfunction "OUT1_3") (pintype "bidirectional"))
      (node (ref "X3") (pin "1") (pinfunction "S_1") (pintype "passive"))
    )
    (net (code "40") (name "Net-(U2-OUT2)") (class "Default")
      (node (ref "U2") (pin "1") (pinfunction "OUT2_1") (pintype "bidirectional"))
      (node (ref "X3") (pin "2") (pinfunction "S_2") (pintype "passive"))
    )
    (net (code "41") (name "Net-(U4-ISENSE)") (class "Default")
      (node (ref "R11") (pin "2") (pinfunction "2_2") (pintype "passive"))
      (node (ref "U4") (pin "2") (pinfunction "ISENSE_2") (pintype "bidirectional"))
    )
    (net (code "42") (name "Net-(U4-OUT1)") (class "Default")
      (node (ref "U4") (pin "3") (pinfunction "OUT1_3") (pintype "bidirectional"))
      (node (ref "X6") (pin "1") (pinfunction "S_1") (pintype "passive"))
    )
    (net (code "43") (name "Net-(U4-OUT2)") (class "Default")
      (node (ref "U4") (pin "1") (pinfunction "OUT2_1") (pintype "bidirectional"))
      (node (ref "X6") (pin "2") (pinfunction "S_2") (pintype "passive"))
    )
    (net (code "44") (name "Net-(U8-ISENSE)") (class "Default")
      (node (ref "R27") (pin "2") (pinfunction "2_2") (pintype "passive"))
      (node (ref "U8") (pin "2") (pinfunction "ISENSE_2") (pintype "bidirectional"))
    )
    (net (code "45") (name "Net-(U8-OUT1)") (class "Default")
      (node (ref "U8") (pin "3") (pinfunction "OUT1_3") (pintype "bidirectional"))
      (node (ref "X12") (pin "1") (pinfunction "S_1") (pintype "passive"))
    )
    (net (code "46") (name "Net-(U8-OUT2)") (class "Default")
      (node (ref "U8") (pin "1") (pinfunction "OUT2_1") (pintype "bidirectional"))
      (node (ref "X12") (pin "2") (pinfunction "S_2") (pintype "passive"))
    )
    (net (code "47") (name "SCL") (class "Default")
      (node (ref "R12") (pin "1") (pinfunction "1_1") (pintype "passive"))
      (node (ref "R28") (pin "1") (pinfunction "1_1") (pintype "passive"))
      (node (ref "R4") (pin "1") (pinfunction "1_1") (pintype "passive"))
      (node (ref "U$16") (pin "19") (pinfunction "SCL_19") (pintype "bidirectional"))
      (node (ref "U$35") (pin "19") (pinfunction "SCL_19") (pintype "bidirectional"))
      (node (ref "U$8") (pin "19") (pinfunction "SCL_19") (pintype "bidirectional"))
      (node (ref "U2") (pin "10") (pinfunction "SCL_10") (pintype "bidirectional"))
      (node (ref "U4") (pin "10") (pinfunction "SCL_10") (pintype "bidirectional"))
      (node (ref "U8") (pin "10") (pinfunction "SCL_10") (pintype "bidirectional"))
      (node (ref "X1") (pin "14") (pinfunction "GPIO4_14") (pintype "bidirectional"))
      (node (ref "X10") (pin "14") (pinfunction "GPIO4_14") (pintype "bidirectional"))
      (node (ref "X4") (pin "14") (pinfunction "GPIO4_14") (pintype "bidirectional"))
    )
    (net (code "48") (name "SDA") (class "Default")
      (node (ref "R13") (pin "1") (pinfunction "1_1") (pintype "passive"))
      (node (ref "R29") (pin "1") (pinfunction "1_1") (pintype "passive"))
      (node (ref "R5") (pin "1") (pinfunction "1_1") (pintype "passive"))
      (node (ref "U$16") (pin "20") (pinfunction "SDA_20") (pintype "bidirectional"))
      (node (ref "U$35") (pin "20") (pinfunction "SDA_20") (pintype "bidirectional"))
      (node (ref "U$8") (pin "20") (pinfunction "SDA_20") (pintype "bidirectional"))
      (node (ref "U2") (pin "9") (pinfunction "SDA_9") (pintype "bidirectional"))
      (node (ref "U4") (pin "9") (pinfunction "SDA_9") (pintype "bidirectional"))
      (node (ref "U8") (pin "9") (pinfunction "SDA_9") (pintype "bidirectional"))
      (node (ref "X1") (pin "13") (pinfunction "GPIO5_13") (pintype "bidirectional"))
      (node (ref "X10") (pin "13") (pinfunction "GPIO5_13") (pintype "bidirectional"))
      (node (ref "X4") (pin "13") (pinfunction "GPIO5_13") (pintype "bidirectional"))
    )
    (net (code "49") (name "VBAT") (class "Default")
      (node (ref "C2") (pin "1") (pinfunction "1_1") (pintype "passive"))
      (node (ref "C4") (pin "1") (pinfunction "1_1") (pintype "passive"))
      (node (ref "C8") (pin "1") (pinfunction "1_1") (pintype "passive"))
      (node (ref "JP1") (pin "2") (pinfunction "2_2") (pintype "passive"))
      (node (ref "JP2") (pin "2") (pinfunction "2_2") (pintype "passive"))
      (node (ref "JP4") (pin "2") (pinfunction "2_2") (pintype "passive"))
      (node (ref "R14") (pin "2") (pinfunction "2_2") (pintype "passive"))
      (node (ref "R30") (pin "2") (pinfunction "2_2") (pintype "passive"))
      (node (ref "R6") (pin "2") (pinfunction "2_2") (pintype "passive"))
      (node (ref "U1") (pin "1") (pinfunction "IN_1") (pintype "power_in"))
      (node (ref "U1") (pin "3") (pinfunction "EN_3") (pintype "input"))
      (node (ref "U2") (pin "4") (pinfunction "VCC_4") (pintype "bidirectional"))
      (node (ref "U3") (pin "1") (pinfunction "IN_1") (pintype "power_in"))
      (node (ref "U3") (pin "3") (pinfunction "EN_3") (pintype "input"))
      (node (ref "U4") (pin "4") (pinfunction "VCC_4") (pintype "bidirectional"))
      (node (ref "U7") (pin "1") (pinfunction "IN_1") (pintype "power_in"))
      (node (ref "U7") (pin "3") (pinfunction "EN_3") (pintype "input"))
      (node (ref "U8") (pin "4") (pinfunction "VCC_4") (pintype "bidirectional"))
      (node (ref "X11") (pin "1") (pinfunction "S_1") (pintype "passive"))
      (node (ref "X2") (pin "1") (pinfunction "S_1") (pintype "passive"))
      (node (ref "X5") (pin "1") (pinfunction "S_1") (pintype "passive"))
    )
    (net (code "50") (name "unconnected-(U$8-SC0-Pad2)") (class "Default")
      (node (ref "U$8") (pin "2") (pinfunction "SC0_2") (pintype "bidirectional"))
    )
    (net (code "51") (name "unconnected-(U$8-SC1-Pad4)") (class "Default")
      (node (ref "U$8") (pin "4") (pinfunction "SC1_4") (pintype "bidirectional"))
    )
    (net (code "52") (name "unconnected-(U$8-SC2-Pad6)") (class "Default")
      (node (ref "U$8") (pin "6") (pinfunction "SC2_6") (pintype "bidirectional"))
    )
    (net (code "53") (name "unconnected-(U$8-SC4-Pad11)") (class "Default")
      (node (ref "U$8") (pin "11") (pinfunction "SC4_11") (pintype "bidirectional"))
    )
    (net (code "54") (name "unconnected-(U$8-SC7-Pad17)") (class "Default")
      (node (ref "U$8") (pin "17") (pinfunction "SC7_17") (pintype "bidirectional"))
    )
    (net (code "55") (name "unconnected-(U$8-SD0-Pad1)") (class "Default")
      (node (ref "U$8") (pin "1") (pinfunction "SD0_1") (pintype "bidirectional"))
    )
    (net (code "56") (name "unconnected-(U$8-SD1-Pad3)") (class "Default")
      (node (ref "U$8") (pin "3") (pinfunction "SD1_3") (pintype "bidirectional"))
    )
    (net (code "57") (name "unconnected-(U$8-SD2-Pad5)") (class "Default")
      (node (ref "U$8") (pin "5") (pinfunction "SD2_5") (pintype "bidirectional"))
    )
    (net (code "58") (name "unconnected-(U$8-SD4-Pad10)") (class "Default")
      (node (ref "U$8") (pin "10") (pinfunction "SD4_10") (pintype "bidirectional"))
    )
    (net (code "59") (name "unconnected-(U$8-SD7-Pad16)") (class "Default")
      (node (ref "U$8") (pin "16") (pinfunction "SD7_16") (pintype "bidirectional"))
    )
    (net (code "60") (name "unconnected-(U$16-SC0-Pad2)") (class "Default")
      (node (ref "U$16") (pin "2") (pinfunction "SC0_2") (pintype "bidirectional"))
    )
    (net (code "61") (name "unconnected-(U$16-SC1-Pad4)") (class "Default")
      (node (ref "U$16") (pin "4") (pinfunction "SC1_4") (pintype "bidirectional"))
    )
    (net (code "62") (name "unconnected-(U$16-SC2-Pad6)") (class "Default")
      (node (ref "U$16") (pin "6") (pinfunction "SC2_6") (pintype "bidirectional"))
    )
    (net (code "63") (name "unconnected-(U$16-SC4-Pad11)") (class "Default")
      (node (ref "U$16") (pin "11") (pinfunction "SC4_11") (pintype "bidirectional"))
    )
    (net (code "64") (name "unconnected-(U$16-SC7-Pad17)") (class "Default")
      (node (ref "U$16") (pin "17") (pinfunction "SC7_17") (pintype "bidirectional"))
    )
    (net (code "65") (name "unconnected-(U$16-SD0-Pad1)") (class "Default")
      (node (ref "U$16") (pin "1") (pinfunction "SD0_1") (pintype "bidirectional"))
    )
    (net (code "66") (name "unconnected-(U$16-SD1-Pad3)") (class "Default")
      (node (ref "U$16") (pin "3") (pinfunction "SD1_3") (pintype "bidirectional"))
    )
    (net (code "67") (name "unconnected-(U$16-SD2-Pad5)") (class "Default")
      (node (ref "U$16") (pin "5") (pinfunction "SD2_5") (pintype "bidirectional"))
    )
    (net (code "68") (name "unconnected-(U$16-SD4-Pad10)") (class "Default")
      (node (ref "U$16") (pin "10") (pinfunction "SD4_10") (pintype "bidirectional"))
    )
    (net (code "69") (name "unconnected-(U$16-SD7-Pad16)") (class "Default")
      (node (ref "U$16") (pin "16") (pinfunction "SD7_16") (pintype "bidirectional"))
    )
    (net (code "70") (name "unconnected-(U$35-SC0-Pad2)") (class "Default")
      (node (ref "U$35") (pin "2") (pinfunction "SC0_2") (pintype "bidirectional"))
    )
    (net (code "71") (name "unconnected-(U$35-SC1-Pad4)") (class "Default")
      (node (ref "U$35") (pin "4") (pinfunction "SC1_4") (pintype "bidirectional"))
    )
    (net (code "72") (name "unconnected-(U$35-SC2-Pad6)") (class "Default")
      (node (ref "U$35") (pin "6") (pinfunction "SC2_6") (pintype "bidirectional"))
    )
    (net (code "73") (name "unconnected-(U$35-SC4-Pad11)") (class "Default")
      (node (ref "U$35") (pin "11") (pinfunction "SC4_11") (pintype "bidirectional"))
    )
    (net (code "74") (name "unconnected-(U$35-SC7-Pad17)") (class "Default")
      (node (ref "U$35") (pin "17") (pinfunction "SC7_17") (pintype "bidirectional"))
    )
    (net (code "75") (name "unconnected-(U$35-SD0-Pad1)") (class "Default")
      (node (ref "U$35") (pin "1") (pinfunction "SD0_1") (pintype "bidirectional"))
    )
    (net (code "76") (name "unconnected-(U$35-SD1-Pad3)") (class "Default")
      (node (ref "U$35") (pin "3") (pinfunction "SD1_3") (pintype "bidirectional"))
    )
    (net (code "77") (name "unconnected-(U$35-SD2-Pad5)") (class "Default")
      (node (ref "U$35") (pin "5") (pinfunction "SD2_5") (pintype "bidirectional"))
    )
    (net (code "78") (name "unconnected-(U$35-SD4-Pad10)") (class "Default")
      (node (ref "U$35") (pin "10") (pinfunction "SD4_10") (pintype "bidirectional"))
    )
    (net (code "79") (name "unconnected-(U$35-SD7-Pad16)") (class "Default")
      (node (ref "U$35") (pin "16") (pinfunction "SD7_16") (pintype "bidirectional"))
    )
    (net (code "80") (name "unconnected-(U1-P4-Pad4)") (class "Default")
      (node (ref "U1") (pin "4") (pinfunction "P4_4") (pintype "bidirectional"))
    )
    (net (code "81") (name "unconnected-(U2-A0-Pad7)") (class "Default")
      (node (ref "U2") (pin "7") (pinfunction "A0_7") (pintype "bidirectional"))
    )
    (net (code "82") (name "unconnected-(U2-A1-Pad8)") (class "Default")
      (node (ref "U2") (pin "8") (pinfunction "A1_8") (pintype "bidirectional"))
    )
    (net (code "83") (name "unconnected-(U3-P4-Pad4)") (class "Default")
      (node (ref "U3") (pin "4") (pinfunction "P4_4") (pintype "bidirectional"))
    )
    (net (code "84") (name "unconnected-(U4-A0-Pad7)") (class "Default")
      (node (ref "U4") (pin "7") (pinfunction "A0_7") (pintype "bidirectional"))
    )
    (net (code "85") (name "unconnected-(U4-A1-Pad8)") (class "Default")
      (node (ref "U4") (pin "8") (pinfunction "A1_8") (pintype "bidirectional"))
    )
    (net (code "86") (name "unconnected-(U7-P4-Pad4)") (class "Default")
      (node (ref "U7") (pin "4") (pinfunction "P4_4") (pintype "bidirectional"))
    )
    (net (code "87") (name "unconnected-(U8-A0-Pad7)") (class "Default")
      (node (ref "U8") (pin "7") (pinfunction "A0_7") (pintype "bidirectional"))
    )
    (net (code "88") (name "unconnected-(U8-A1-Pad8)") (class "Default")
      (node (ref "U8") (pin "8") (pinfunction "A1_8") (pintype "bidirectional"))
    )
  )
)
